# SmartDevice_2020-07-31_15-30-18.net
KiCad netlist of a schematic drawn in EasyEDA
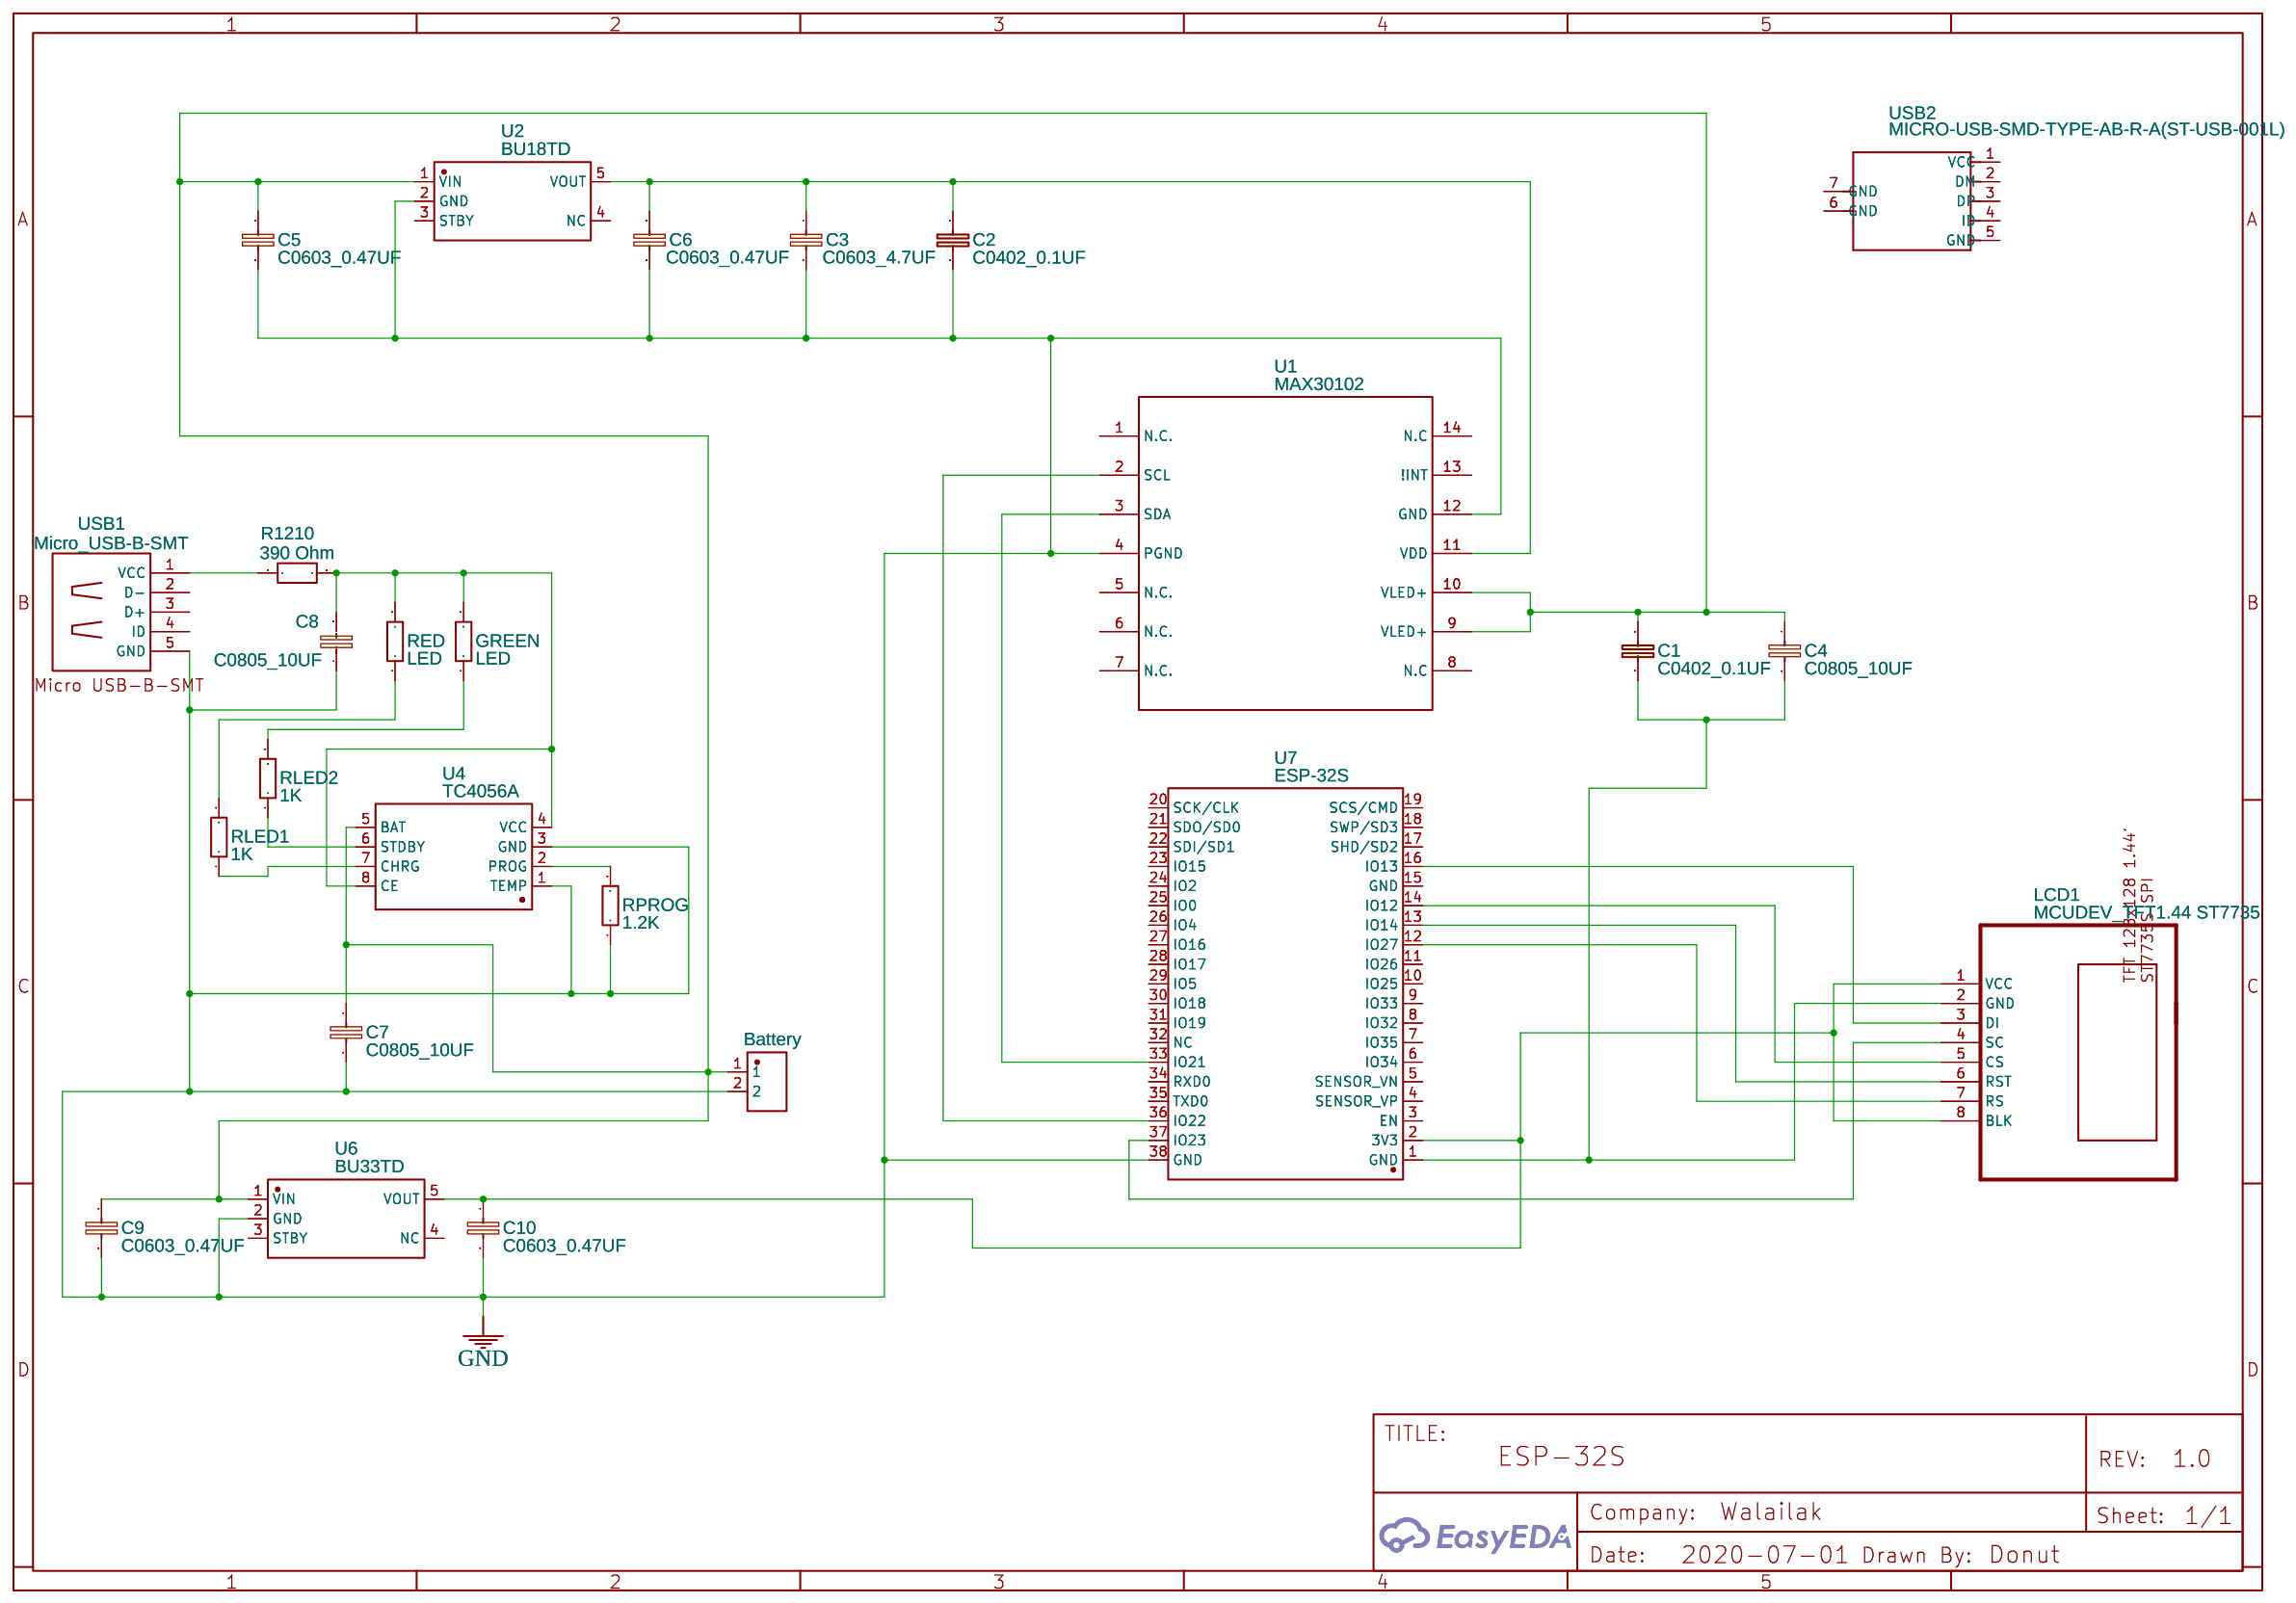
[diagram p0: schematic sheet]

(export (version "E")
  (design (tool "Eeschema 10.0.6"))
  (components
    (comp (ref "C1") (value "C0402_0.1UF") (libsource (lib "") (part "0.1UF-16V(+-10%)(0402)")))
    (comp (ref "C2") (value "C0402_0.1UF") (libsource (lib "") (part "0.1UF-16V(+-10%)(0402)")))
    (comp (ref "C3") (value "C0603_4.7UF") (libsource (lib "") (part "C0603_0.47UF")))
    (comp (ref "C4") (value "C0805_10UF") (libsource (lib "") (part "10UF-0805-10V-10%")))
    (comp (ref "C5") (value "C0603_0.47UF") (libsource (lib "") (part "C0603_0.47UF")))
    (comp (ref "C6") (value "C0603_0.47UF") (libsource (lib "") (part "C0603_0.47UF")))
    (comp (ref "C7") (value "C0805_10UF") (libsource (lib "") (part "10UF-0805-10V-10%")))
    (comp (ref "C8") (value "C0805_10UF") (libsource (lib "") (part "10UF-0805-10V-10%_1")))
    (comp (ref "C9") (value "C0603_0.47UF") (libsource (lib "") (part "C0603_0.47UF")))
    (comp (ref "C10") (value "C0603_0.47UF") (libsource (lib "") (part "C0603_0.47UF")))
    (comp (ref "GREEN")
      (value "LED")
      (fields
        (field (name "BOM_Manufacturer Part") "MELF-MFR02041/4WS41.2KΩFT50")
        (field (name "BOM_Supplier Part") "C265932")
      )
      (libsource (lib "") (part "MELF-MFR02041/4WS41.2KΩFT50_1"))
    )
    (comp (ref "LCD1") (value "MCUDEV_TFT1.44 ST7735") (libsource (lib "") (part "MCUDEV_TFT1.44 ST7735")))
    (comp (ref "R1210")
      (value "390 Ohm")
      (fields
        (field (name "BOM_Manufacturer Part") "1210W2F1210T5E")
        (field (name "BOM_Supplier Part") "C422419")
      )
      (libsource (lib "") (part "1210W2F1210T5E"))
    )
    (comp (ref "RED")
      (value "LED")
      (fields
        (field (name "BOM_Manufacturer Part") "MELF-MFR02041/4WS41.2KΩFT50")
        (field (name "BOM_Supplier Part") "C265932")
      )
      (libsource (lib "") (part "MELF-MFR02041/4WS41.2KΩFT50_3"))
    )
    (comp (ref "RLED1")
      (value "1K")
      (fields
        (field (name "BOM_Manufacturer Part") "MELF-MFR02041/4WS41.2KΩFT50")
        (field (name "BOM_Supplier Part") "C265932")
      )
      (libsource (lib "") (part "MELF-MFR02041/4WS41.2KΩFT50"))
    )
    (comp (ref "RLED2")
      (value "1K")
      (fields
        (field (name "BOM_Manufacturer Part") "MELF-MFR02041/4WS41.2KΩFT50")
        (field (name "BOM_Supplier Part") "C265932")
      )
      (libsource (lib "") (part "MELF-MFR02041/4WS41.2KΩFT50"))
    )
    (comp (ref "RPROG")
      (value "1.2K")
      (fields
        (field (name "BOM_Manufacturer Part") "MELF-MFR02041/4WS41.2KΩFT50")
        (field (name "BOM_Supplier Part") "C265932")
      )
      (libsource (lib "") (part "MELF-MFR02041/4WS41.2KΩFT50_2"))
    )
    (comp (ref "U1")
      (value "MAX30102")
      (fields
        (field (name "BOM_Manufacturer Part") "92Y9295")
        (field (name "BOM_Supplier Part") "MAX30101EFD+")
      )
      (libsource (lib "") (part "MAX30102"))
    )
    (comp (ref "U2")
      (value "BU18TD")
      (fields
        (field (name "BOM_Manufacturer Part") "BD4825G-TR")
        (field (name "BOM_Supplier Part") "C123010")
      )
      (libsource (lib "") (part "SSOP-5_CM_Copy"))
    )
    (comp (ref "U3")
      (value "Battery")
      (fields
        (field (name "BOM_Manufacturer Part") "KF127R-5.08-2P")
        (field (name "BOM_Supplier Part") "C474910")
      )
      (libsource (lib "") (part "KF127R-5.08-2P"))
    )
    (comp (ref "U4") (value "TC4056A") (libsource (lib "") (part "TC4056A")))
    (comp (ref "U6")
      (value "BU33TD")
      (fields
        (field (name "BOM_Manufacturer Part") "BD4825G-TR")
        (field (name "BOM_Supplier Part") "C123010")
      )
      (libsource (lib "") (part "SSOP-5_CM_Copy"))
    )
    (comp (ref "U7")
      (value "ESP-32S")
      (fields (field (name "BOM_Supplier Part") "C82899"))
      (libsource (lib "") (part "ESP-32S"))
    )
    (comp (ref "USB1")
      (value "Micro_USB-B-SMT")
      (fields (field (name "BOM_Supplier Part") "C21377"))
      (libsource (lib "") (part "Micro_USB-B-SMT"))
    )
    (comp (ref "USB2")
      (value "MICRO-USB-SMD-TYPE-AB-R-A(ST-USB-001L)")
      (fields (field (name "BOM_Manufacturer Part") "?"))
      (libsource (lib "") (part "MICRO-USB-SMD-TYPE-AB-R-A(ST-USB-001L)"))
    )
  )
  (nets
    (net (code "1") (name "GND") (class "Default")
      (node (ref "C10") (pin "2") (pinfunction "2_2") (pintype "bidirectional"))
      (node (ref "C2") (pin "2") (pinfunction "2_2") (pintype "unspecified"))
      (node (ref "C3") (pin "2") (pinfunction "2_2") (pintype "bidirectional"))
      (node (ref "C5") (pin "2") (pinfunction "2_2") (pintype "bidirectional"))
      (node (ref "C6") (pin "2") (pinfunction "2_2") (pintype "bidirectional"))
      (node (ref "C7") (pin "2") (pinfunction "2_2") (pintype "bidirectional"))
      (node (ref "C8") (pin "1") (pinfunction "1_1") (pintype "bidirectional"))
      (node (ref "C9") (pin "2") (pinfunction "2_2") (pintype "bidirectional"))
      (node (ref "RPROG") (pin "1") (pinfunction "1_1") (pintype "unspecified"))
      (node (ref "U1") (pin "12") (pinfunction "GND_12") (pintype "unspecified"))
      (node (ref "U1") (pin "4") (pinfunction "PGND_4") (pintype "unspecified"))
      (node (ref "U2") (pin "2") (pinfunction "GND_2") (pintype "unspecified"))
      (node (ref "U3") (pin "2") (pinfunction "2_2") (pintype "unspecified"))
      (node (ref "U4") (pin "1") (pinfunction "TEMP_1") (pintype "unspecified"))
      (node (ref "U4") (pin "3") (pinfunction "GND_3") (pintype "unspecified"))
      (node (ref "U6") (pin "2") (pinfunction "GND_2") (pintype "unspecified"))
      (node (ref "U7") (pin "38") (pinfunction "GND_38") (pintype "unspecified"))
      (node (ref "USB1") (pin "5") (pinfunction "GND_5") (pintype "unspecified"))
    )
    (net (code "2") (name "Net-(GREEN-Pad1)") (class "Default")
      (node (ref "GREEN") (pin "1") (pinfunction "1_1") (pintype "unspecified"))
      (node (ref "RLED2") (pin "2") (pinfunction "2_2") (pintype "unspecified"))
    )
    (net (code "3") (name "Net-(LCD1-BLK)") (class "Default")
      (node (ref "C10") (pin "1") (pinfunction "1_1") (pintype "bidirectional"))
      (node (ref "LCD1") (pin "1") (pinfunction "VCC_1") (pintype "output"))
      (node (ref "LCD1") (pin "8") (pinfunction "BLK_8") (pintype "input"))
      (node (ref "U6") (pin "5") (pinfunction "VOUT_5") (pintype "unspecified"))
      (node (ref "U7") (pin "2") (pinfunction "3V3_2") (pintype "unspecified"))
    )
    (net (code "4") (name "Net-(LCD1-CS)") (class "Default")
      (node (ref "LCD1") (pin "5") (pinfunction "CS_5") (pintype "unspecified"))
      (node (ref "U7") (pin "14") (pinfunction "IO12_14") (pintype "unspecified"))
    )
    (net (code "5") (name "Net-(LCD1-DI)") (class "Default")
      (node (ref "LCD1") (pin "3") (pinfunction "DI_3") (pintype "input"))
      (node (ref "U7") (pin "16") (pinfunction "IO13_16") (pintype "unspecified"))
    )
    (net (code "6") (name "Net-(LCD1-GND)") (class "Default")
      (node (ref "C1") (pin "2") (pinfunction "2_2") (pintype "unspecified"))
      (node (ref "C4") (pin "2") (pinfunction "2_2") (pintype "bidirectional"))
      (node (ref "LCD1") (pin "2") (pinfunction "GND_2") (pintype "passive"))
      (node (ref "U7") (pin "1") (pinfunction "GND_1") (pintype "unspecified"))
    )
    (net (code "7") (name "Net-(LCD1-RS)") (class "Default")
      (node (ref "LCD1") (pin "7") (pinfunction "RS_7") (pintype "input"))
      (node (ref "U7") (pin "12") (pinfunction "IO27_12") (pintype "unspecified"))
    )
    (net (code "8") (name "Net-(LCD1-RST)") (class "Default")
      (node (ref "LCD1") (pin "6") (pinfunction "RST_6") (pintype "input"))
      (node (ref "U7") (pin "13") (pinfunction "IO14_13") (pintype "unspecified"))
    )
    (net (code "9") (name "Net-(LCD1-SC)") (class "Default")
      (node (ref "LCD1") (pin "4") (pinfunction "SC_4") (pintype "input"))
      (node (ref "U7") (pin "37") (pinfunction "IO23_37") (pintype "unspecified"))
    )
    (net (code "10") (name "Net-(RED-Pad1)") (class "Default")
      (node (ref "RED") (pin "1") (pinfunction "1_1") (pintype "unspecified"))
      (node (ref "RLED1") (pin "2") (pinfunction "2_2") (pintype "unspecified"))
    )
    (net (code "11") (name "Net-(U1-SCL)") (class "Default")
      (node (ref "U1") (pin "2") (pinfunction "SCL_2") (pintype "unspecified"))
      (node (ref "U7") (pin "36") (pinfunction "IO22_36") (pintype "unspecified"))
    )
    (net (code "12") (name "Net-(U1-SDA)") (class "Default")
      (node (ref "U1") (pin "3") (pinfunction "SDA_3") (pintype "unspecified"))
      (node (ref "U7") (pin "33") (pinfunction "IO21_33") (pintype "unspecified"))
    )
    (net (code "13") (name "Net-(U1-VDD)") (class "Default")
      (node (ref "C2") (pin "1") (pinfunction "1_1") (pintype "unspecified"))
      (node (ref "C3") (pin "1") (pinfunction "1_1") (pintype "bidirectional"))
      (node (ref "C6") (pin "1") (pinfunction "1_1") (pintype "bidirectional"))
      (node (ref "U1") (pin "11") (pinfunction "VDD_11") (pintype "unspecified"))
      (node (ref "U2") (pin "5") (pinfunction "VOUT_5") (pintype "unspecified"))
    )
    (net (code "14") (name "Net-(U2-VIN)") (class "Default")
      (node (ref "C1") (pin "1") (pinfunction "1_1") (pintype "unspecified"))
      (node (ref "C4") (pin "1") (pinfunction "1_1") (pintype "bidirectional"))
      (node (ref "C5") (pin "1") (pinfunction "1_1") (pintype "bidirectional"))
      (node (ref "C7") (pin "1") (pinfunction "1_1") (pintype "bidirectional"))
      (node (ref "C9") (pin "1") (pinfunction "1_1") (pintype "bidirectional"))
      (node (ref "U1") (pin "10") (pinfunction "VLED+_10") (pintype "unspecified"))
      (node (ref "U1") (pin "9") (pinfunction "VLED+_9") (pintype "unspecified"))
      (node (ref "U2") (pin "1") (pinfunction "VIN_1") (pintype "unspecified"))
      (node (ref "U3") (pin "1") (pinfunction "1_1") (pintype "unspecified"))
      (node (ref "U4") (pin "5") (pinfunction "BAT_5") (pintype "unspecified"))
      (node (ref "U6") (pin "1") (pinfunction "VIN_1") (pintype "unspecified"))
    )
    (net (code "15") (name "Net-(U4-CE)") (class "Default")
      (node (ref "C8") (pin "2") (pinfunction "2_2") (pintype "bidirectional"))
      (node (ref "GREEN") (pin "2") (pinfunction "2_2") (pintype "unspecified"))
      (node (ref "R1210") (pin "2") (pinfunction "2_2") (pintype "unspecified"))
      (node (ref "RED") (pin "2") (pinfunction "2_2") (pintype "unspecified"))
      (node (ref "U4") (pin "4") (pinfunction "VCC_4") (pintype "unspecified"))
      (node (ref "U4") (pin "8") (pinfunction "CE_8") (pintype "unspecified"))
    )
    (net (code "16") (name "Net-(U4-CHRG)") (class "Default")
      (node (ref "RLED1") (pin "1") (pinfunction "1_1") (pintype "unspecified"))
      (node (ref "U4") (pin "7") (pinfunction "CHRG_7") (pintype "unspecified"))
    )
    (net (code "17") (name "Net-(U4-PROG)") (class "Default")
      (node (ref "RPROG") (pin "2") (pinfunction "2_2") (pintype "unspecified"))
      (node (ref "U4") (pin "2") (pinfunction "PROG_2") (pintype "unspecified"))
    )
    (net (code "18") (name "Net-(U4-STDBY)") (class "Default")
      (node (ref "RLED2") (pin "1") (pinfunction "1_1") (pintype "unspecified"))
      (node (ref "U4") (pin "6") (pinfunction "STDBY_6") (pintype "unspecified"))
    )
    (net (code "19") (name "Net-(USB1-VCC)") (class "Default")
      (node (ref "R1210") (pin "1") (pinfunction "1_1") (pintype "unspecified"))
      (node (ref "USB1") (pin "1") (pinfunction "VCC_1") (pintype "unspecified"))
    )
    (net (code "20") (name "unconnected-(U1-!INT-Pad13)") (class "Default")
      (node (ref "U1") (pin "13") (pinfunction "!INT_13") (pintype "unspecified"))
    )
    (net (code "21") (name "unconnected-(U1-N.C-Pad8)") (class "Default")
      (node (ref "U1") (pin "8") (pinfunction "N.C_8") (pintype "unspecified"))
    )
    (net (code "22") (name "unconnected-(U1-N.C-Pad14)") (class "Default")
      (node (ref "U1") (pin "14") (pinfunction "N.C_14") (pintype "unspecified"))
    )
    (net (code "23") (name "unconnected-(U1-N.C.-Pad1)") (class "Default")
      (node (ref "U1") (pin "1") (pinfunction "N.C._1") (pintype "unspecified"))
    )
    (net (code "24") (name "unconnected-(U1-N.C.-Pad5)") (class "Default")
      (node (ref "U1") (pin "5") (pinfunction "N.C._5") (pintype "unspecified"))
    )
    (net (code "25") (name "unconnected-(U1-N.C.-Pad6)") (class "Default")
      (node (ref "U1") (pin "6") (pinfunction "N.C._6") (pintype "unspecified"))
    )
    (net (code "26") (name "unconnected-(U1-N.C.-Pad7)") (class "Default")
      (node (ref "U1") (pin "7") (pinfunction "N.C._7") (pintype "unspecified"))
    )
    (net (code "27") (name "unconnected-(U2-NC-Pad4)") (class "Default")
      (node (ref "U2") (pin "4") (pinfunction "NC_4") (pintype "unspecified"))
    )
    (net (code "28") (name "unconnected-(U2-STBY-Pad3)") (class "Default")
      (node (ref "U2") (pin "3") (pinfunction "STBY_3") (pintype "unspecified"))
    )
    (net (code "29") (name "unconnected-(U6-NC-Pad4)") (class "Default")
      (node (ref "U6") (pin "4") (pinfunction "NC_4") (pintype "unspecified"))
    )
    (net (code "30") (name "unconnected-(U6-STBY-Pad3)") (class "Default")
      (node (ref "U6") (pin "3") (pinfunction "STBY_3") (pintype "unspecified"))
    )
    (net (code "31") (name "unconnected-(U7-EN-Pad3)") (class "Default")
      (node (ref "U7") (pin "3") (pinfunction "EN_3") (pintype "unspecified"))
    )
    (net (code "32") (name "unconnected-(U7-GND-Pad15)") (class "Default")
      (node (ref "U7") (pin "15") (pinfunction "GND_15") (pintype "unspecified"))
    )
    (net (code "33") (name "unconnected-(U7-IO0-Pad25)") (class "Default")
      (node (ref "U7") (pin "25") (pinfunction "IO0_25") (pintype "unspecified"))
    )
    (net (code "34") (name "unconnected-(U7-IO2-Pad24)") (class "Default")
      (node (ref "U7") (pin "24") (pinfunction "IO2_24") (pintype "unspecified"))
    )
    (net (code "35") (name "unconnected-(U7-IO4-Pad26)") (class "Default")
      (node (ref "U7") (pin "26") (pinfunction "IO4_26") (pintype "unspecified"))
    )
    (net (code "36") (name "unconnected-(U7-IO5-Pad29)") (class "Default")
      (node (ref "U7") (pin "29") (pinfunction "IO5_29") (pintype "unspecified"))
    )
    (net (code "37") (name "unconnected-(U7-IO15-Pad23)") (class "Default")
      (node (ref "U7") (pin "23") (pinfunction "IO15_23") (pintype "unspecified"))
    )
    (net (code "38") (name "unconnected-(U7-IO16-Pad27)") (class "Default")
      (node (ref "U7") (pin "27") (pinfunction "IO16_27") (pintype "unspecified"))
    )
    (net (code "39") (name "unconnected-(U7-IO17-Pad28)") (class "Default")
      (node (ref "U7") (pin "28") (pinfunction "IO17_28") (pintype "unspecified"))
    )
    (net (code "40") (name "unconnected-(U7-IO18-Pad30)") (class "Default")
      (node (ref "U7") (pin "30") (pinfunction "IO18_30") (pintype "unspecified"))
    )
    (net (code "41") (name "unconnected-(U7-IO19-Pad31)") (class "Default")
      (node (ref "U7") (pin "31") (pinfunction "IO19_31") (pintype "unspecified"))
    )
    (net (code "42") (name "unconnected-(U7-IO25-Pad10)") (class "Default")
      (node (ref "U7") (pin "10") (pinfunction "IO25_10") (pintype "unspecified"))
    )
    (net (code "43") (name "unconnected-(U7-IO26-Pad11)") (class "Default")
      (node (ref "U7") (pin "11") (pinfunction "IO26_11") (pintype "unspecified"))
    )
    (net (code "44") (name "unconnected-(U7-IO32-Pad8)") (class "Default")
      (node (ref "U7") (pin "8") (pinfunction "IO32_8") (pintype "unspecified"))
    )
    (net (code "45") (name "unconnected-(U7-IO33-Pad9)") (class "Default")
      (node (ref "U7") (pin "9") (pinfunction "IO33_9") (pintype "unspecified"))
    )
    (net (code "46") (name "unconnected-(U7-IO34-Pad6)") (class "Default")
      (node (ref "U7") (pin "6") (pinfunction "IO34_6") (pintype "unspecified"))
    )
    (net (code "47") (name "unconnected-(U7-IO35-Pad7)") (class "Default")
      (node (ref "U7") (pin "7") (pinfunction "IO35_7") (pintype "unspecified"))
    )
    (net (code "48") (name "unconnected-(U7-NC-Pad32)") (class "Default")
      (node (ref "U7") (pin "32") (pinfunction "NC_32") (pintype "unspecified"))
    )
    (net (code "49") (name "unconnected-(U7-RXD0-Pad34)") (class "Default")
      (node (ref "U7") (pin "34") (pinfunction "RXD0_34") (pintype "unspecified"))
    )
    (net (code "50") (name "unconnected-(U7-SCK{slash}CLK-Pad20)") (class "Default")
      (node (ref "U7") (pin "20") (pinfunction "SCK/CLK_20") (pintype "unspecified"))
    )
    (net (code "51") (name "unconnected-(U7-SCS{slash}CMD-Pad19)") (class "Default")
      (node (ref "U7") (pin "19") (pinfunction "SCS/CMD_19") (pintype "unspecified"))
    )
    (net (code "52") (name "unconnected-(U7-SDI{slash}SD1-Pad22)") (class "Default")
      (node (ref "U7") (pin "22") (pinfunction "SDI/SD1_22") (pintype "unspecified"))
    )
    (net (code "53") (name "unconnected-(U7-SDO{slash}SD0-Pad21)") (class "Default")
      (node (ref "U7") (pin "21") (pinfunction "SDO/SD0_21") (pintype "unspecified"))
    )
    (net (code "54") (name "unconnected-(U7-SENSOR_VN-Pad5)") (class "Default")
      (node (ref "U7") (pin "5") (pinfunction "SENSOR_VN_5") (pintype "unspecified"))
    )
    (net (code "55") (name "unconnected-(U7-SENSOR_VP-Pad4)") (class "Default")
      (node (ref "U7") (pin "4") (pinfunction "SENSOR_VP_4") (pintype "unspecified"))
    )
    (net (code "56") (name "unconnected-(U7-SHD{slash}SD2-Pad17)") (class "Default")
      (node (ref "U7") (pin "17") (pinfunction "SHD/SD2_17") (pintype "unspecified"))
    )
    (net (code "57") (name "unconnected-(U7-SWP{slash}SD3-Pad18)") (class "Default")
      (node (ref "U7") (pin "18") (pinfunction "SWP/SD3_18") (pintype "unspecified"))
    )
    (net (code "58") (name "unconnected-(U7-TXD0-Pad35)") (class "Default")
      (node (ref "U7") (pin "35") (pinfunction "TXD0_35") (pintype "unspecified"))
    )
    (net (code "59") (name "unconnected-(USB1-D+-Pad3)") (class "Default")
      (node (ref "USB1") (pin "3") (pinfunction "D+_3") (pintype "unspecified"))
    )
    (net (code "60") (name "unconnected-(USB1-D--Pad2)") (class "Default")
      (node (ref "USB1") (pin "2") (pinfunction "D-_2") (pintype "unspecified"))
    )
    (net (code "61") (name "unconnected-(USB1-ID-Pad4)") (class "Default")
      (node (ref "USB1") (pin "4") (pinfunction "ID_4") (pintype "unspecified"))
    )
    (net (code "62") (name "unconnected-(USB2-DM-Pad2)") (class "Default")
      (node (ref "USB2") (pin "2") (pinfunction "DM_2") (pintype "unspecified"))
    )
    (net (code "63") (name "unconnected-(USB2-DP-Pad3)") (class "Default")
      (node (ref "USB2") (pin "3") (pinfunction "DP_3") (pintype "unspecified"))
    )
    (net (code "64") (name "unconnected-(USB2-GND-Pad5)") (class "Default")
      (node (ref "USB2") (pin "5") (pinfunction "GND_5") (pintype "unspecified"))
    )
    (net (code "65") (name "unconnected-(USB2-GND-Pad6)") (class "Default")
      (node (ref "USB2") (pin "6") (pinfunction "GND_6") (pintype "unspecified"))
    )
    (net (code "66") (name "unconnected-(USB2-GND-Pad7)") (class "Default")
      (node (ref "USB2") (pin "7") (pinfunction "GND_7") (pintype "unspecified"))
    )
    (net (code "67") (name "unconnected-(USB2-ID-Pad4)") (class "Default")
      (node (ref "USB2") (pin "4") (pinfunction "ID_4") (pintype "unspecified"))
    )
    (net (code "68") (name "unconnected-(USB2-VCC-Pad1)") (class "Default")
      (node (ref "USB2") (pin "1") (pinfunction "VCC_1") (pintype "unspecified"))
    )
  )
)
